# avrstick-uSD-shield.net
KiCad netlist of a schematic drawn in EAGLE
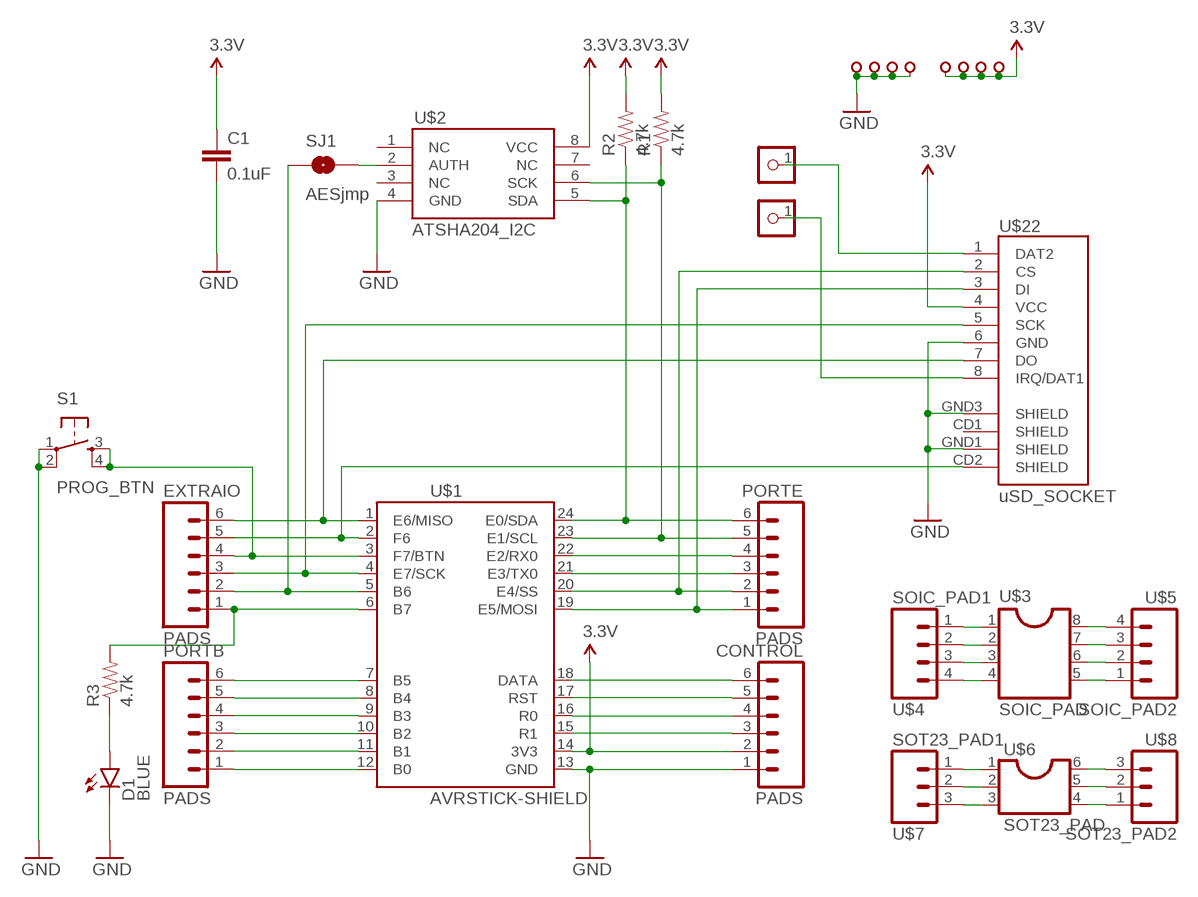
[diagram p0: schematic, sheet 1]

(export (version "E")
  (design (tool "Eeschema 10.0.6"))
  (components
    (comp (ref "C1")
      (value "0.1uF")
      (footprint "eagle-import:1206")
      (libsource (lib "eagle-import") (part "CAP1206"))
    )
    (comp (ref "CONTROL")
      (value "PADS")
      (footprint "eagle-import:M06_SIDESILK_B")
      (libsource (lib "eagle-import") (part "M06_SIDESILK_BOT"))
    )
    (comp (ref "D1")
      (value "BLUE")
      (footprint "eagle-import:LED-1206")
      (libsource (lib "eagle-import") (part "LED-BLUE1206"))
    )
    (comp (ref "EXTRAIO")
      (value "PADS")
      (footprint "eagle-import:M06_SIDESILK_T")
      (libsource (lib "eagle-import") (part "M06_SIDESILK_TOP"))
    )
    (comp (ref "J1")
      (value "CON_HEADER_1X01-SMD")
      (footprint "eagle-import:SMDPAD05X05")
      (libsource (lib "eagle-import") (part "CON_HEADER_1X01-SMD"))
    )
    (comp (ref "J2")
      (value "CON_HEADER_1X01-SMD")
      (footprint "eagle-import:SMDPAD05X05")
      (libsource (lib "eagle-import") (part "CON_HEADER_1X01-SMD"))
    )
    (comp (ref "PORTB")
      (value "PADS")
      (footprint "eagle-import:M06_SIDESILK_T")
      (libsource (lib "eagle-import") (part "M06_SIDESILK_TOP"))
    )
    (comp (ref "PORTE")
      (value "PADS")
      (footprint "eagle-import:M06_SIDESILK_B")
      (libsource (lib "eagle-import") (part "M06_SIDESILK_BOT"))
    )
    (comp (ref "R1")
      (value "4.7k")
      (footprint "eagle-import:1206")
      (libsource (lib "eagle-import") (part "RESISTOR1206"))
    )
    (comp (ref "R2")
      (value "4.7k")
      (footprint "eagle-import:1206")
      (libsource (lib "eagle-import") (part "RESISTOR1206"))
    )
    (comp (ref "R3")
      (value "4.7k")
      (footprint "eagle-import:1206")
      (libsource (lib "eagle-import") (part "RESISTOR1206"))
    )
    (comp (ref "S1")
      (value "PROG_BTN")
      (footprint "eagle-import:TACTILE-SWITCH-SMD")
      (libsource (lib "eagle-import") (part "TAC_SWITCHSMD"))
    )
    (comp (ref "SJ1")
      (value "AESjmp")
      (footprint "eagle-import:PAD-JUMPER-2-NO_YES_SILK")
      (libsource (lib "eagle-import") (part "JUMPER-PAD-2-NOYES_SILK"))
    )
    (comp (ref "U$1")
      (value "AVRSTICK-SHIELD")
      (footprint "eagle-import:AVRSTICK-SHIELD")
      (libsource (lib "eagle-import") (part "AVRSTICK-SHIELD"))
    )
    (comp (ref "U$2")
      (value "ATSHA204_I2C")
      (footprint "eagle-import:SOIC-8-NARROW")
      (libsource (lib "eagle-import") (part "ATAES132_I2C"))
    )
    (comp (ref "U$3")
      (value "SOIC_PAD")
      (footprint "eagle-import:SOIC-8-NARROW")
      (libsource (lib "eagle-import") (part "IC-8PINSOIC-8"))
    )
    (comp (ref "U$4")
      (value "SOIC_PAD1")
      (footprint "eagle-import:M04_SILK_1SQ")
      (libsource (lib "eagle-import") (part "M04_SILK_1SQ"))
    )
    (comp (ref "U$5")
      (value "SOIC_PAD2")
      (footprint "eagle-import:M04_SILK")
      (libsource (lib "eagle-import") (part "M04_SILK"))
    )
    (comp (ref "U$6")
      (value "SOT23_PAD")
      (footprint "eagle-import:SOT23-6")
      (libsource (lib "eagle-import") (part "IC-6PINSOT23-6"))
    )
    (comp (ref "U$7")
      (value "SOT23_PAD1")
      (footprint "eagle-import:M03_SILK_1SQ")
      (libsource (lib "eagle-import") (part "M03_SILK_1SQ"))
    )
    (comp (ref "U$8")
      (value "SOT23_PAD2")
      (footprint "eagle-import:M03_SILK")
      (libsource (lib "eagle-import") (part "M03_SILK"))
    )
    (comp (ref "U$9")
      (value "M01_SIDESILK")
      (footprint "eagle-import:M01_SIDESILK")
      (libsource (lib "eagle-import") (part "M01_SIDESILK"))
    )
    (comp (ref "U$10")
      (value "M01_SIDESILK")
      (footprint "eagle-import:M01_SIDESILK")
      (libsource (lib "eagle-import") (part "M01_SIDESILK"))
    )
    (comp (ref "U$11")
      (value "M01_SIDESILK")
      (footprint "eagle-import:M01_SIDESILK")
      (libsource (lib "eagle-import") (part "M01_SIDESILK"))
    )
    (comp (ref "U$12")
      (value "M01_SIDESILK")
      (footprint "eagle-import:M01_SIDESILK")
      (libsource (lib "eagle-import") (part "M01_SIDESILK"))
    )
    (comp (ref "U$13")
      (value "M01_SIDESILK")
      (footprint "eagle-import:M01_SIDESILK")
      (libsource (lib "eagle-import") (part "M01_SIDESILK"))
    )
    (comp (ref "U$14")
      (value "M01_SIDESILK")
      (footprint "eagle-import:M01_SIDESILK")
      (libsource (lib "eagle-import") (part "M01_SIDESILK"))
    )
    (comp (ref "U$15")
      (value "M01_NOSILK")
      (footprint "eagle-import:M01_NOSILK")
      (libsource (lib "eagle-import") (part "M01_NOSILK"))
    )
    (comp (ref "U$16")
      (value "M01_NOSILK")
      (footprint "eagle-import:M01_NOSILK")
      (libsource (lib "eagle-import") (part "M01_NOSILK"))
    )
    (comp (ref "U$22")
      (value "uSD_SOCKET")
      (footprint "eagle-import:MICROSD_SOCKET_SPARKFUN")
      (libsource (lib "eagle-import") (part "MICROSD_SOCKET_SPARKFUN"))
    )
  )
  (nets
    (net (code "1") (name "3.3V") (class "Default")
      (node (ref "C1") (pin "1") (pinfunction "1_1") (pintype "passive"))
      (node (ref "CONTROL") (pin "2") (pinfunction "2_2") (pintype "passive"))
      (node (ref "R1") (pin "2") (pinfunction "2_2") (pintype "passive"))
      (node (ref "R2") (pin "2") (pinfunction "2_2") (pintype "passive"))
      (node (ref "U$1") (pin "14") (pinfunction "3V3_14") (pintype "bidirectional"))
      (node (ref "U$12") (pin "1") (pinfunction "1_1") (pintype "bidirectional"))
      (node (ref "U$13") (pin "1") (pinfunction "1_1") (pintype "bidirectional"))
      (node (ref "U$14") (pin "1") (pinfunction "1_1") (pintype "bidirectional"))
      (node (ref "U$16") (pin "1") (pinfunction "1_1") (pintype "bidirectional"))
      (node (ref "U$2") (pin "8") (pinfunction "VCC_8") (pintype "bidirectional"))
      (node (ref "U$22") (pin "4") (pinfunction "VCC_4") (pintype "bidirectional"))
    )
    (net (code "2") (name "GND") (class "Default")
      (node (ref "C1") (pin "2") (pinfunction "2_2") (pintype "passive"))
      (node (ref "CONTROL") (pin "1") (pinfunction "1_1") (pintype "passive"))
      (node (ref "D1") (pin "C") (pinfunction "C_C") (pintype "passive"))
      (node (ref "S1") (pin "1") (pinfunction "1_1") (pintype "passive"))
      (node (ref "S1") (pin "2") (pinfunction "2_2") (pintype "passive"))
      (node (ref "U$1") (pin "13") (pinfunction "GND_13") (pintype "bidirectional"))
      (node (ref "U$10") (pin "1") (pinfunction "1_1") (pintype "bidirectional"))
      (node (ref "U$11") (pin "1") (pinfunction "1_1") (pintype "bidirectional"))
      (node (ref "U$15") (pin "1") (pinfunction "1_1") (pintype "bidirectional"))
      (node (ref "U$2") (pin "4") (pinfunction "GND_4") (pintype "bidirectional"))
      (node (ref "U$22") (pin "6") (pinfunction "GND_6") (pintype "bidirectional"))
      (node (ref "U$22") (pin "GND1") (pinfunction "SHIELD_GND1") (pintype "bidirectional"))
      (node (ref "U$22") (pin "GND3") (pinfunction "SHIELD_GND3") (pintype "bidirectional"))
      (node (ref "U$9") (pin "1") (pinfunction "1_1") (pintype "bidirectional"))
    )
    (net (code "3") (name "Net-(D1-PadA)") (class "Default")
      (node (ref "D1") (pin "A") (pinfunction "A_A") (pintype "passive"))
      (node (ref "R3") (pin "1") (pinfunction "1_1") (pintype "passive"))
    )
    (net (code "4") (name "Net-(U$1-B0)") (class "Default")
      (node (ref "PORTB") (pin "1") (pinfunction "1_1") (pintype "passive"))
      (node (ref "U$1") (pin "12") (pinfunction "B0_12") (pintype "bidirectional"))
    )
    (net (code "5") (name "Net-(U$1-B1)") (class "Default")
      (node (ref "PORTB") (pin "2") (pinfunction "2_2") (pintype "passive"))
      (node (ref "U$1") (pin "11") (pinfunction "B1_11") (pintype "bidirectional"))
    )
    (net (code "6") (name "Net-(U$1-B2)") (class "Default")
      (node (ref "PORTB") (pin "3") (pinfunction "3_3") (pintype "passive"))
      (node (ref "U$1") (pin "10") (pinfunction "B2_10") (pintype "bidirectional"))
    )
    (net (code "7") (name "Net-(U$1-B3)") (class "Default")
      (node (ref "PORTB") (pin "4") (pinfunction "4_4") (pintype "passive"))
      (node (ref "U$1") (pin "9") (pinfunction "B3_9") (pintype "bidirectional"))
    )
    (net (code "8") (name "Net-(U$1-B4)") (class "Default")
      (node (ref "PORTB") (pin "5") (pinfunction "5_5") (pintype "passive"))
      (node (ref "U$1") (pin "8") (pinfunction "B4_8") (pintype "bidirectional"))
    )
    (net (code "9") (name "Net-(U$1-B5)") (class "Default")
      (node (ref "PORTB") (pin "6") (pinfunction "6_6") (pintype "passive"))
      (node (ref "U$1") (pin "7") (pinfunction "B5_7") (pintype "bidirectional"))
    )
    (net (code "10") (name "Net-(U$1-B6)") (class "Default")
      (node (ref "EXTRAIO") (pin "2") (pinfunction "2_2") (pintype "passive"))
      (node (ref "SJ1") (pin "1") (pinfunction "1_1") (pintype "passive"))
      (node (ref "U$1") (pin "5") (pinfunction "B6_5") (pintype "bidirectional"))
    )
    (net (code "11") (name "Net-(U$1-B7)") (class "Default")
      (node (ref "EXTRAIO") (pin "1") (pinfunction "1_1") (pintype "passive"))
      (node (ref "R3") (pin "2") (pinfunction "2_2") (pintype "passive"))
      (node (ref "U$1") (pin "6") (pinfunction "B7_6") (pintype "bidirectional"))
    )
    (net (code "12") (name "Net-(U$1-DATA)") (class "Default")
      (node (ref "CONTROL") (pin "6") (pinfunction "6_6") (pintype "passive"))
      (node (ref "U$1") (pin "18") (pinfunction "DATA_18") (pintype "bidirectional"))
    )
    (net (code "13") (name "Net-(U$1-E0{slash}SDA)") (class "Default")
      (node (ref "PORTE") (pin "6") (pinfunction "6_6") (pintype "passive"))
      (node (ref "R2") (pin "1") (pinfunction "1_1") (pintype "passive"))
      (node (ref "U$1") (pin "24") (pinfunction "E0/SDA_24") (pintype "bidirectional"))
      (node (ref "U$2") (pin "5") (pinfunction "SDA_5") (pintype "bidirectional"))
    )
    (net (code "14") (name "Net-(U$1-E1{slash}SCL)") (class "Default")
      (node (ref "PORTE") (pin "5") (pinfunction "5_5") (pintype "passive"))
      (node (ref "R1") (pin "1") (pinfunction "1_1") (pintype "passive"))
      (node (ref "U$1") (pin "23") (pinfunction "E1/SCL_23") (pintype "bidirectional"))
      (node (ref "U$2") (pin "6") (pinfunction "SCK_6") (pintype "input"))
    )
    (net (code "15") (name "Net-(U$1-E2{slash}RX0)") (class "Default")
      (node (ref "PORTE") (pin "4") (pinfunction "4_4") (pintype "passive"))
      (node (ref "U$1") (pin "22") (pinfunction "E2/RX0_22") (pintype "bidirectional"))
    )
    (net (code "16") (name "Net-(U$1-E3{slash}TX0)") (class "Default")
      (node (ref "PORTE") (pin "3") (pinfunction "3_3") (pintype "passive"))
      (node (ref "U$1") (pin "21") (pinfunction "E3/TX0_21") (pintype "bidirectional"))
    )
    (net (code "17") (name "Net-(U$1-E4{slash}SS)") (class "Default")
      (node (ref "PORTE") (pin "2") (pinfunction "2_2") (pintype "passive"))
      (node (ref "U$1") (pin "20") (pinfunction "E4/SS_20") (pintype "bidirectional"))
      (node (ref "U$22") (pin "2") (pinfunction "CS_2") (pintype "bidirectional"))
    )
    (net (code "18") (name "Net-(U$1-E5{slash}MOSI)") (class "Default")
      (node (ref "PORTE") (pin "1") (pinfunction "1_1") (pintype "passive"))
      (node (ref "U$1") (pin "19") (pinfunction "E5/MOSI_19") (pintype "bidirectional"))
      (node (ref "U$22") (pin "3") (pinfunction "DI_3") (pintype "bidirectional"))
    )
    (net (code "19") (name "Net-(U$1-E6{slash}MISO)") (class "Default")
      (node (ref "EXTRAIO") (pin "6") (pinfunction "6_6") (pintype "passive"))
      (node (ref "U$1") (pin "1") (pinfunction "E6/MISO_1") (pintype "bidirectional"))
      (node (ref "U$22") (pin "7") (pinfunction "DO_7") (pintype "bidirectional"))
    )
    (net (code "20") (name "Net-(U$1-E7{slash}SCK)") (class "Default")
      (node (ref "EXTRAIO") (pin "3") (pinfunction "3_3") (pintype "passive"))
      (node (ref "U$1") (pin "4") (pinfunction "E7/SCK_4") (pintype "bidirectional"))
      (node (ref "U$22") (pin "5") (pinfunction "SCK_5") (pintype "bidirectional"))
    )
    (net (code "21") (name "Net-(U$1-F6)") (class "Default")
      (node (ref "EXTRAIO") (pin "5") (pinfunction "5_5") (pintype "passive"))
      (node (ref "U$1") (pin "2") (pinfunction "F6_2") (pintype "bidirectional"))
      (node (ref "U$22") (pin "CD2") (pinfunction "SHIELD_CD2") (pintype "bidirectional"))
    )
    (net (code "22") (name "Net-(U$1-F7{slash}BTN)") (class "Default")
      (node (ref "EXTRAIO") (pin "4") (pinfunction "4_4") (pintype "passive"))
      (node (ref "S1") (pin "3") (pinfunction "3_3") (pintype "passive"))
      (node (ref "S1") (pin "4") (pinfunction "4_4") (pintype "passive"))
      (node (ref "U$1") (pin "3") (pinfunction "F7/BTN_3") (pintype "bidirectional"))
    )
    (net (code "23") (name "Net-(U$1-R0)") (class "Default")
      (node (ref "CONTROL") (pin "4") (pinfunction "4_4") (pintype "passive"))
      (node (ref "U$1") (pin "16") (pinfunction "R0_16") (pintype "bidirectional"))
    )
    (net (code "24") (name "Net-(U$1-R1)") (class "Default")
      (node (ref "CONTROL") (pin "3") (pinfunction "3_3") (pintype "passive"))
      (node (ref "U$1") (pin "15") (pinfunction "R1_15") (pintype "bidirectional"))
    )
    (net (code "25") (name "Net-(U$1-RST)") (class "Default")
      (node (ref "CONTROL") (pin "5") (pinfunction "5_5") (pintype "passive"))
      (node (ref "U$1") (pin "17") (pinfunction "RST_17") (pintype "bidirectional"))
    )
    (net (code "26") (name "Net-(U$2-AUTH)") (class "Default")
      (node (ref "SJ1") (pin "2") (pinfunction "2_2") (pintype "passive"))
      (node (ref "U$2") (pin "2") (pinfunction "AUTH_2") (pintype "output"))
    )
    (net (code "27") (name "Net-(U$3-Pad1)") (class "Default")
      (node (ref "U$3") (pin "1") (pinfunction "1_1") (pintype "bidirectional"))
      (node (ref "U$4") (pin "1") (pinfunction "1_1") (pintype "passive"))
    )
    (net (code "28") (name "Net-(U$3-Pad2)") (class "Default")
      (node (ref "U$3") (pin "2") (pinfunction "2_2") (pintype "bidirectional"))
      (node (ref "U$4") (pin "2") (pinfunction "2_2") (pintype "passive"))
    )
    (net (code "29") (name "Net-(U$3-Pad3)") (class "Default")
      (node (ref "U$3") (pin "3") (pinfunction "3_3") (pintype "bidirectional"))
      (node (ref "U$4") (pin "3") (pinfunction "3_3") (pintype "passive"))
    )
    (net (code "30") (name "Net-(U$3-Pad4)") (class "Default")
      (node (ref "U$3") (pin "4") (pinfunction "4_4") (pintype "bidirectional"))
      (node (ref "U$4") (pin "4") (pinfunction "4_4") (pintype "passive"))
    )
    (net (code "31") (name "Net-(U$3-Pad5)") (class "Default")
      (node (ref "U$3") (pin "5") (pinfunction "5_5") (pintype "bidirectional"))
      (node (ref "U$5") (pin "1") (pinfunction "1_1") (pintype "passive"))
    )
    (net (code "32") (name "Net-(U$3-Pad6)") (class "Default")
      (node (ref "U$3") (pin "6") (pinfunction "6_6") (pintype "bidirectional"))
      (node (ref "U$5") (pin "2") (pinfunction "2_2") (pintype "passive"))
    )
    (net (code "33") (name "Net-(U$3-Pad7)") (class "Default")
      (node (ref "U$3") (pin "7") (pinfunction "7_7") (pintype "bidirectional"))
      (node (ref "U$5") (pin "3") (pinfunction "3_3") (pintype "passive"))
    )
    (net (code "34") (name "Net-(U$3-Pad8)") (class "Default")
      (node (ref "U$3") (pin "8") (pinfunction "8_8") (pintype "bidirectional"))
      (node (ref "U$5") (pin "4") (pinfunction "4_4") (pintype "passive"))
    )
    (net (code "35") (name "Net-(U$6-Pad1)") (class "Default")
      (node (ref "U$6") (pin "1") (pinfunction "1_1") (pintype "passive"))
      (node (ref "U$7") (pin "1") (pinfunction "1_1") (pintype "passive"))
    )
    (net (code "36") (name "Net-(U$6-Pad2)") (class "Default")
      (node (ref "U$6") (pin "2") (pinfunction "2_2") (pintype "passive"))
      (node (ref "U$7") (pin "2") (pinfunction "2_2") (pintype "passive"))
    )
    (net (code "37") (name "Net-(U$6-Pad3)") (class "Default")
      (node (ref "U$6") (pin "3") (pinfunction "3_3") (pintype "passive"))
      (node (ref "U$7") (pin "3") (pinfunction "3_3") (pintype "passive"))
    )
    (net (code "38") (name "Net-(U$6-Pad4)") (class "Default")
      (node (ref "U$6") (pin "4") (pinfunction "4_4") (pintype "passive"))
      (node (ref "U$8") (pin "1") (pinfunction "1_1") (pintype "passive"))
    )
    (net (code "39") (name "Net-(U$6-Pad5)") (class "Default")
      (node (ref "U$6") (pin "5") (pinfunction "5_5") (pintype "passive"))
      (node (ref "U$8") (pin "2") (pinfunction "2_2") (pintype "passive"))
    )
    (net (code "40") (name "Net-(U$6-Pad6)") (class "Default")
      (node (ref "U$6") (pin "6") (pinfunction "6_6") (pintype "passive"))
      (node (ref "U$8") (pin "3") (pinfunction "3_3") (pintype "passive"))
    )
    (net (code "41") (name "Net-(U$22-DAT2)") (class "Default")
      (node (ref "J1") (pin "1") (pinfunction "1_1") (pintype "passive"))
      (node (ref "U$22") (pin "1") (pinfunction "DAT2_1") (pintype "bidirectional"))
    )
    (net (code "42") (name "Net-(U$22-IRQ{slash}DAT1)") (class "Default")
      (node (ref "J2") (pin "1") (pinfunction "1_1") (pintype "passive"))
      (node (ref "U$22") (pin "8") (pinfunction "IRQ/DAT1_8") (pintype "bidirectional"))
    )
    (net (code "43") (name "unconnected-(U$2-NC-Pad1)") (class "Default")
      (node (ref "U$2") (pin "1") (pinfunction "NC_1") (pintype "no_connect"))
    )
    (net (code "44") (name "unconnected-(U$2-NC-Pad3)") (class "Default")
      (node (ref "U$2") (pin "3") (pinfunction "NC_3") (pintype "no_connect"))
    )
    (net (code "45") (name "unconnected-(U$2-NC-Pad7)") (class "Default")
      (node (ref "U$2") (pin "7") (pinfunction "NC_7") (pintype "no_connect"))
    )
    (net (code "46") (name "unconnected-(U$22-SHIELD-PadCD1)") (class "Default")
      (node (ref "U$22") (pin "CD1") (pinfunction "SHIELD_CD1") (pintype "bidirectional"))
    )
  )
)
